# modFOC-Sensing.net
KiCad netlist of a schematic drawn in Altium Designer
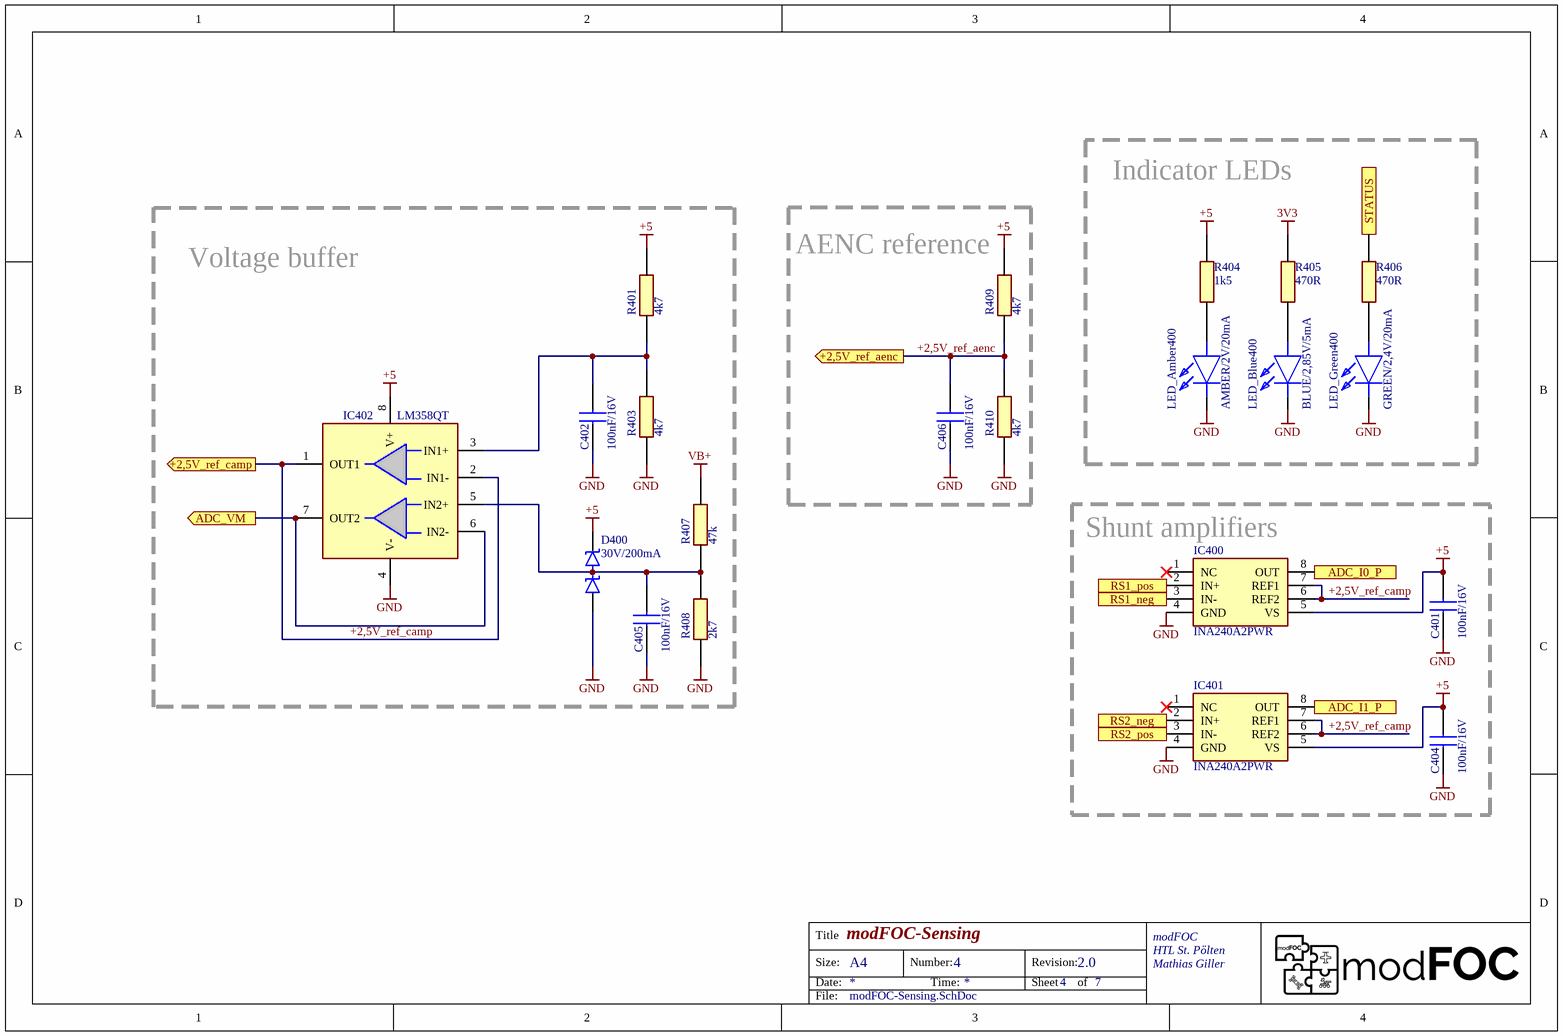
[diagram p0: modFOC-Sensing.SchDoc]

(export (version "E")
  (design (tool "Eeschema 10.0.6"))
  (components
    (comp (ref "C401")
      (value "100nF/16V")
      (footprint "CAPC1608X97N")
      (description "Capacitor")
      (libsource (lib "Schlib1") (part "C0603"))
    )
    (comp (ref "C402")
      (value "100nF/16V")
      (footprint "CAPC1608X97N")
      (description "Capacitor")
      (libsource (lib "Schlib1") (part "C0603"))
    )
    (comp (ref "C404")
      (value "100nF/16V")
      (footprint "CAPC1608X97N")
      (description "Capacitor")
      (libsource (lib "Schlib1") (part "C0603"))
    )
    (comp (ref "C405")
      (value "100nF/16V")
      (footprint "CAPC1608X97N")
      (description "Capacitor")
      (libsource (lib "Schlib1") (part "C0603"))
    )
    (comp (ref "C406")
      (value "100nF/16V")
      (footprint "CAPC1608X97N")
      (description "Capacitor")
      (libsource (lib "Schlib1") (part "C0603"))
    )
    (comp (ref "D400")
      (value "30V/200mA")
      (footprint "SOT95P240X110-3N")
      (description "Schottky Diode")
      (fields
        (field (name "MANUFACTURER_PART_NUMBER") "BAT54S")
        (field (name "MOUSER PART NUMBER") "583-BAT54S")
      )
      (libsource (lib "Schlib1") (part "BAT54S"))
    )
    (comp (ref "IC400")
      (value "INA240A2PWR")
      (footprint "SOP65P640X120-8N")
      (description "Current shunt amp")
      (fields
        (field (name "MANUFACTURER_PART_NUMBER") "INA240A4PWR")
        (field (name "MOUSER PART NUMBER") "595-INA240A4PWR")
      )
      (libsource (lib "Schlib1") (part "INA240A2PWR"))
    )
    (comp (ref "IC401")
      (value "INA240A2PWR")
      (footprint "SOP65P640X120-8N")
      (description "Current shunt amp")
      (fields
        (field (name "MANUFACTURER_PART_NUMBER") "INA240A4PWR")
        (field (name "MOUSER PART NUMBER") "595-INA240A4PWR")
      )
      (libsource (lib "Schlib1") (part "INA240A2PWR"))
    )
    (comp (ref "IC402")
      (value "LM358QT")
      (footprint "PcbLib1:SON50P200X200X60-9N-D")
      (description "Le' Megaslow 358")
      (fields (field (name "MOUSER PART NUMBER") "511-LM358QT"))
      (libsource (lib "Schlib1") (part "LM358QT"))
    )
    (comp (ref "LED_Amber400")
      (value "AMBER/2V/20mA")
      (footprint "LEDC1608X55N")
      (description "LED")
      (fields
        (field (name "MANUFACTURER_PART_NUMBER") "ASMT-RA45-AP932")
        (field (name "MOUSER PART NUMBER") "630-ASMT-RA45-AP932")
      )
      (libsource (lib "Schlib1") (part "ASMT-RA45-AP932"))
    )
    (comp (ref "LED_Blue400")
      (value "BLUE/2,85V/5mA")
      (footprint "LEDC1608X40N")
      (description "LED")
      (fields
        (field (name "MANUFACTURER_PART_NUMBER") "LB Q39G-L2OO-35-1")
        (field (name "MOUSER PART NUMBER") "720-LBQ39GL2N2351")
      )
      (libsource (lib "Schlib1") (part "LB_Q39G-L2OO-35-1"))
    )
    (comp (ref "LED_Green400")
      (value "GREEN/2,4V/20mA")
      (footprint "LGQ396PS35")
      (description "LED Green")
      (fields
        (field (name "MANUFACTURER_PART_NUMBER") "LG Q396-PS-35")
        (field (name "MOUSER PART NUMBER") "720-LGQ396A3964")
      )
      (libsource (lib "Schlib1") (part "LG_Q396-PS-35"))
    )
    (comp (ref "R401")
      (value "4k7")
      (footprint "RESC1608X55N")
      (description "Resistor")
      (libsource (lib "") (part "R0603_1"))
    )
    (comp (ref "R403")
      (value "4k7")
      (footprint "RESC1608X55N")
      (description "Resistor")
      (libsource (lib "") (part "R0603_1"))
    )
    (comp (ref "R404")
      (value "1k5")
      (footprint "RESC1608X55N")
      (description "Resistor")
      (libsource (lib "Schlib1") (part "R0603"))
    )
    (comp (ref "R405")
      (value "470R")
      (footprint "RESC1608X55N")
      (description "Resistor")
      (libsource (lib "Schlib1") (part "R0603"))
    )
    (comp (ref "R406")
      (value "470R")
      (footprint "RESC1608X55N")
      (description "Resistor")
      (libsource (lib "Schlib1") (part "R0603"))
    )
    (comp (ref "R407")
      (value "47k")
      (footprint "RESC1608X55N")
      (description "Resistor")
      (libsource (lib "Schlib1") (part "R0603"))
    )
    (comp (ref "R408")
      (value "2k7")
      (footprint "RESC1608X55N")
      (description "Resistor")
      (libsource (lib "Schlib1") (part "R0603"))
    )
    (comp (ref "R409")
      (value "4k7")
      (footprint "RESC1608X55N")
      (description "Resistor")
      (libsource (lib "") (part "R0603_1"))
    )
    (comp (ref "R410")
      (value "4k7")
      (footprint "RESC1608X55N")
      (description "Resistor")
      (libsource (lib "") (part "R0603_1"))
    )
  )
  (nets
    (net (code "1") (name "+5") (class "Default")
      (node (ref "C401") (pin "2") (pinfunction "2_2") (pintype "passive"))
      (node (ref "C404") (pin "2") (pinfunction "2_2") (pintype "passive"))
      (node (ref "D400") (pin "2") (pinfunction "K_2") (pintype "passive"))
      (node (ref "IC400") (pin "5") (pinfunction "VS_5") (pintype "power_in"))
      (node (ref "IC401") (pin "5") (pinfunction "VS_5") (pintype "power_in"))
      (node (ref "IC402") (pin "8") (pinfunction "V+_8") (pintype "passive"))
      (node (ref "R401") (pin "2") (pinfunction "2_2") (pintype "passive"))
      (node (ref "R404") (pin "1") (pinfunction "1_1") (pintype "passive"))
      (node (ref "R409") (pin "2") (pinfunction "2_2") (pintype "passive"))
    )
    (net (code "2") (name "/+2,5V_ref_aenc") (class "Default")
      (node (ref "C406") (pin "2") (pinfunction "2_2") (pintype "passive"))
      (node (ref "R409") (pin "1") (pinfunction "1_1") (pintype "passive"))
      (node (ref "R410") (pin "2") (pinfunction "2_2") (pintype "passive"))
    )
    (net (code "3") (name "/+2,5V_ref_camp") (class "Default")
      (node (ref "IC400") (pin "6") (pinfunction "REF2_6") (pintype "passive"))
      (node (ref "IC400") (pin "7") (pinfunction "REF1_7") (pintype "passive"))
      (node (ref "IC401") (pin "6") (pinfunction "REF2_6") (pintype "passive"))
      (node (ref "IC401") (pin "7") (pinfunction "REF1_7") (pintype "passive"))
      (node (ref "IC402") (pin "1") (pinfunction "OUT1_1") (pintype "passive"))
      (node (ref "IC402") (pin "2") (pinfunction "IN1-_2") (pintype "passive"))
    )
    (net (code "4") (name "/ADC_I0_P") (class "Default")
      (node (ref "IC400") (pin "8") (pinfunction "OUT_8") (pintype "passive"))
    )
    (net (code "5") (name "/ADC_I1_P") (class "Default")
      (node (ref "IC401") (pin "8") (pinfunction "OUT_8") (pintype "passive"))
    )
    (net (code "6") (name "/ADC_VM") (class "Default")
      (node (ref "IC402") (pin "6") (pinfunction "IN2-_6") (pintype "passive"))
      (node (ref "IC402") (pin "7") (pinfunction "OUT2_7") (pintype "passive"))
    )
    (net (code "7") (name "/RS1_neg") (class "Default")
      (node (ref "IC400") (pin "3") (pinfunction "IN-_3") (pintype "passive"))
    )
    (net (code "8") (name "/RS1_pos") (class "Default")
      (node (ref "IC400") (pin "2") (pinfunction "IN+_2") (pintype "passive"))
    )
    (net (code "9") (name "/RS2_neg") (class "Default")
      (node (ref "IC401") (pin "2") (pinfunction "IN+_2") (pintype "passive"))
    )
    (net (code "10") (name "/RS2_pos") (class "Default")
      (node (ref "IC401") (pin "3") (pinfunction "IN-_3") (pintype "passive"))
    )
    (net (code "11") (name "/STATUS") (class "Default")
      (node (ref "R406") (pin "1") (pinfunction "1_1") (pintype "passive"))
    )
    (net (code "12") (name "3V3") (class "Default")
      (node (ref "R405") (pin "1") (pinfunction "1_1") (pintype "passive"))
    )
    (net (code "13") (name "GND") (class "Default")
      (node (ref "C401") (pin "1") (pinfunction "1_1") (pintype "passive"))
      (node (ref "C402") (pin "1") (pinfunction "1_1") (pintype "passive"))
      (node (ref "C404") (pin "1") (pinfunction "1_1") (pintype "passive"))
      (node (ref "C405") (pin "1") (pinfunction "1_1") (pintype "passive"))
      (node (ref "C406") (pin "1") (pinfunction "1_1") (pintype "passive"))
      (node (ref "D400") (pin "1") (pinfunction "A_1") (pintype "passive"))
      (node (ref "IC400") (pin "4") (pinfunction "GND_4") (pintype "power_in"))
      (node (ref "IC401") (pin "4") (pinfunction "GND_4") (pintype "power_in"))
      (node (ref "IC402") (pin "4") (pinfunction "V-_4") (pintype "passive"))
      (node (ref "LED_Amber400") (pin "1") (pinfunction "K_1") (pintype "passive"))
      (node (ref "LED_Blue400") (pin "1") (pinfunction "K_1") (pintype "passive"))
      (node (ref "LED_Green400") (pin "1") (pinfunction "K_1") (pintype "passive"))
      (node (ref "R403") (pin "1") (pinfunction "1_1") (pintype "passive"))
      (node (ref "R408") (pin "2") (pinfunction "2_2") (pintype "passive"))
      (node (ref "R410") (pin "1") (pinfunction "1_1") (pintype "passive"))
    )
    (net (code "14") (name "Net-(D400-A{slash}K)") (class "Default")
      (node (ref "C405") (pin "2") (pinfunction "2_2") (pintype "passive"))
      (node (ref "D400") (pin "3") (pinfunction "A/K_3") (pintype "passive"))
      (node (ref "IC402") (pin "5") (pinfunction "IN2+_5") (pintype "passive"))
      (node (ref "R407") (pin "2") (pinfunction "2_2") (pintype "passive"))
      (node (ref "R408") (pin "1") (pinfunction "1_1") (pintype "passive"))
    )
    (net (code "15") (name "Net-(IC402-IN1+)") (class "Default")
      (node (ref "C402") (pin "2") (pinfunction "2_2") (pintype "passive"))
      (node (ref "IC402") (pin "3") (pinfunction "IN1+_3") (pintype "passive"))
      (node (ref "R401") (pin "1") (pinfunction "1_1") (pintype "passive"))
      (node (ref "R403") (pin "2") (pinfunction "2_2") (pintype "passive"))
    )
    (net (code "16") (name "Net-(LED_Amber400-A)") (class "Default")
      (node (ref "LED_Amber400") (pin "2") (pinfunction "A_2") (pintype "passive"))
      (node (ref "R404") (pin "2") (pinfunction "2_2") (pintype "passive"))
    )
    (net (code "17") (name "Net-(LED_Blue400-A)") (class "Default")
      (node (ref "LED_Blue400") (pin "2") (pinfunction "A_2") (pintype "passive"))
      (node (ref "R405") (pin "2") (pinfunction "2_2") (pintype "passive"))
    )
    (net (code "18") (name "Net-(LED_Green400-A)") (class "Default")
      (node (ref "LED_Green400") (pin "2") (pinfunction "A_2") (pintype "passive"))
      (node (ref "R406") (pin "2") (pinfunction "2_2") (pintype "passive"))
    )
    (net (code "19") (name "VB+") (class "Default")
      (node (ref "R407") (pin "1") (pinfunction "1_1") (pintype "passive"))
    )
    (net (code "20") (name "unconnected-(IC400-NC-Pad1)") (class "Default")
      (node (ref "IC400") (pin "1") (pinfunction "NC_1") (pintype "passive+no_connect"))
    )
    (net (code "21") (name "unconnected-(IC401-NC-Pad1)") (class "Default")
      (node (ref "IC401") (pin "1") (pinfunction "NC_1") (pintype "passive+no_connect"))
    )
  )
)
